# satshakit_micro.net
KiCad netlist of a schematic drawn in EAGLE
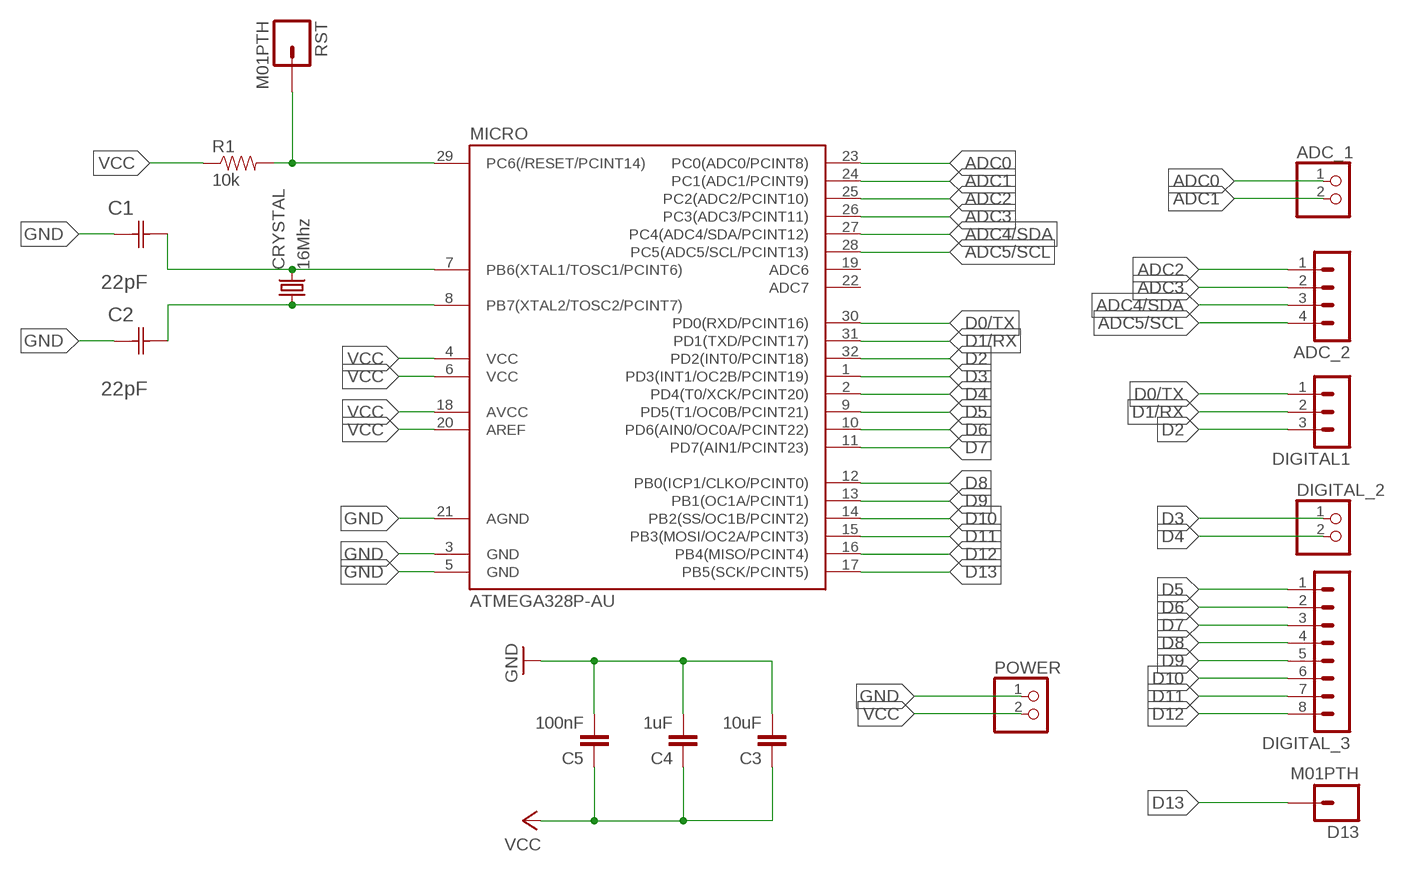
[diagram p0: schematic, sheet 1]

(export (version "E")
  (design (tool "Eeschema 10.0.6"))
  (components
    (comp (ref "ADC_1")
      (value "PINHD-1X2")
      (footprint "eagle-import:1X02")
      (libsource (lib "eagle-import") (part "PINHD-1X2"))
    )
    (comp (ref "ADC_2")
      (value "MA04-1")
      (footprint "eagle-import:MA04-1")
      (libsource (lib "eagle-import") (part "MA04-1"))
    )
    (comp (ref "C1")
      (value "22pF")
      (footprint "eagle-import:CAPC3216X178N")
      (fields (field (name "MPN") "0612ZC225MAT2A") (field (name "TOLERANCE") "±20%"))
      (libsource (lib "eagle-import") (part "0612ZC225MAT2A"))
    )
    (comp (ref "C2")
      (value "22pF")
      (footprint "eagle-import:CAPC3216X178N")
      (fields (field (name "MPN") "0612ZC225MAT2A") (field (name "TOLERANCE") "±20%"))
      (libsource (lib "eagle-import") (part "0612ZC225MAT2A"))
    )
    (comp (ref "C3")
      (value "10uF")
      (footprint "eagle-import:1206")
      (libsource (lib "eagle-import") (part "CAP1206"))
    )
    (comp (ref "C4")
      (value "1uF")
      (footprint "eagle-import:1206")
      (libsource (lib "eagle-import") (part "CAP1206"))
    )
    (comp (ref "C5")
      (value "100nF")
      (footprint "eagle-import:1206")
      (libsource (lib "eagle-import") (part "CAP1206"))
    )
    (comp (ref "CRYSTAL")
      (value "16Mhz")
      (footprint "eagle-import:CSM-7X-DU")
      (libsource (lib "eagle-import") (part "CSM-7X-DU"))
    )
    (comp (ref "D13")
      (value "M01PTH")
      (footprint "eagle-import:1X01")
      (libsource (lib "eagle-import") (part "M01PTH"))
    )
    (comp (ref "DIGITAL1")
      (value "MA03-1")
      (footprint "eagle-import:MA03-1")
      (libsource (lib "eagle-import") (part "MA03-1"))
    )
    (comp (ref "DIGITAL_2")
      (value "PINHD-1X2")
      (footprint "eagle-import:1X02")
      (libsource (lib "eagle-import") (part "PINHD-1X2"))
    )
    (comp (ref "DIGITAL_3")
      (value "MA08-1")
      (footprint "eagle-import:MA08-1")
      (libsource (lib "eagle-import") (part "MA08-1"))
    )
    (comp (ref "MICRO")
      (value "ATMEGA328P-AU")
      (footprint "eagle-import:TQFP32-08")
      (libsource (lib "eagle-import") (part "ATMEGA48/88/168-AU"))
    )
    (comp (ref "POWER")
      (value "PINHD-1X2")
      (footprint "eagle-import:1X02")
      (libsource (lib "eagle-import") (part "PINHD-1X2"))
    )
    (comp (ref "R1")
      (value "10k")
      (footprint "eagle-import:1206")
      (libsource (lib "eagle-import") (part "RESISTOR1206"))
    )
    (comp (ref "RST")
      (value "M01PTH")
      (footprint "eagle-import:1X01")
      (libsource (lib "eagle-import") (part "M01PTH"))
    )
  )
  (nets
    (net (code "1") (name "ADC0") (class "Default")
      (node (ref "ADC_1") (pin "1") (pinfunction "1_1") (pintype "passive"))
      (node (ref "MICRO") (pin "23") (pinfunction "PC0(ADC0/PCINT8)_23") (pintype "bidirectional"))
    )
    (net (code "2") (name "ADC1") (class "Default")
      (node (ref "ADC_1") (pin "2") (pinfunction "2_2") (pintype "passive"))
      (node (ref "MICRO") (pin "24") (pinfunction "PC1(ADC1/PCINT9)_24") (pintype "bidirectional"))
    )
    (net (code "3") (name "ADC2") (class "Default")
      (node (ref "ADC_2") (pin "1") (pinfunction "1_1") (pintype "passive"))
      (node (ref "MICRO") (pin "25") (pinfunction "PC2(ADC2/PCINT10)_25") (pintype "bidirectional"))
    )
    (net (code "4") (name "ADC3") (class "Default")
      (node (ref "ADC_2") (pin "2") (pinfunction "2_2") (pintype "passive"))
      (node (ref "MICRO") (pin "26") (pinfunction "PC3(ADC3/PCINT11)_26") (pintype "bidirectional"))
    )
    (net (code "5") (name "ADC4{slash}SDA") (class "Default")
      (node (ref "ADC_2") (pin "3") (pinfunction "3_3") (pintype "passive"))
      (node (ref "MICRO") (pin "27") (pinfunction "PC4(ADC4/SDA/PCINT12)_27") (pintype "bidirectional"))
    )
    (net (code "6") (name "ADC5{slash}SCL") (class "Default")
      (node (ref "ADC_2") (pin "4") (pinfunction "4_4") (pintype "passive"))
      (node (ref "MICRO") (pin "28") (pinfunction "PC5(ADC5/SCL/PCINT13)_28") (pintype "bidirectional"))
    )
    (net (code "7") (name "D0{slash}TX") (class "Default")
      (node (ref "DIGITAL1") (pin "1") (pinfunction "1_1") (pintype "passive"))
      (node (ref "MICRO") (pin "30") (pinfunction "PD0(RXD/PCINT16)_30") (pintype "bidirectional"))
    )
    (net (code "8") (name "D1{slash}RX") (class "Default")
      (node (ref "DIGITAL1") (pin "2") (pinfunction "2_2") (pintype "passive"))
      (node (ref "MICRO") (pin "31") (pinfunction "PD1(TXD/PCINT17)_31") (pintype "bidirectional"))
    )
    (net (code "9") (name "D2") (class "Default")
      (node (ref "DIGITAL1") (pin "3") (pinfunction "3_3") (pintype "passive"))
      (node (ref "MICRO") (pin "32") (pinfunction "PD2(INT0/PCINT18)_32") (pintype "bidirectional"))
    )
    (net (code "10") (name "D3") (class "Default")
      (node (ref "DIGITAL_2") (pin "1") (pinfunction "1_1") (pintype "passive"))
      (node (ref "MICRO") (pin "1") (pinfunction "PD3(INT1/OC2B/PCINT19)_1") (pintype "bidirectional"))
    )
    (net (code "11") (name "D4") (class "Default")
      (node (ref "DIGITAL_2") (pin "2") (pinfunction "2_2") (pintype "passive"))
      (node (ref "MICRO") (pin "2") (pinfunction "PD4(T0/XCK/PCINT20)_2") (pintype "bidirectional"))
    )
    (net (code "12") (name "D5") (class "Default")
      (node (ref "DIGITAL_3") (pin "1") (pinfunction "1_1") (pintype "passive"))
      (node (ref "MICRO") (pin "9") (pinfunction "PD5(T1/OC0B/PCINT21)_9") (pintype "bidirectional"))
    )
    (net (code "13") (name "D6") (class "Default")
      (node (ref "DIGITAL_3") (pin "2") (pinfunction "2_2") (pintype "passive"))
      (node (ref "MICRO") (pin "10") (pinfunction "PD6(AIN0/OC0A/PCINT22)_10") (pintype "bidirectional"))
    )
    (net (code "14") (name "D7") (class "Default")
      (node (ref "DIGITAL_3") (pin "3") (pinfunction "3_3") (pintype "passive"))
      (node (ref "MICRO") (pin "11") (pinfunction "PD7(AIN1/PCINT23)_11") (pintype "bidirectional"))
    )
    (net (code "15") (name "D8") (class "Default")
      (node (ref "DIGITAL_3") (pin "4") (pinfunction "4_4") (pintype "passive"))
      (node (ref "MICRO") (pin "12") (pinfunction "PB0(ICP1/CLKO/PCINT0)_12") (pintype "bidirectional"))
    )
    (net (code "16") (name "D9") (class "Default")
      (node (ref "DIGITAL_3") (pin "5") (pinfunction "5_5") (pintype "passive"))
      (node (ref "MICRO") (pin "13") (pinfunction "PB1(OC1A/PCINT1)_13") (pintype "bidirectional"))
    )
    (net (code "17") (name "D10") (class "Default")
      (node (ref "DIGITAL_3") (pin "6") (pinfunction "6_6") (pintype "passive"))
      (node (ref "MICRO") (pin "14") (pinfunction "PB2(SS/OC1B/PCINT2)_14") (pintype "bidirectional"))
    )
    (net (code "18") (name "D11") (class "Default")
      (node (ref "DIGITAL_3") (pin "7") (pinfunction "7_7") (pintype "passive"))
      (node (ref "MICRO") (pin "15") (pinfunction "PB3(MOSI/OC2A/PCINT3)_15") (pintype "bidirectional"))
    )
    (net (code "19") (name "D12") (class "Default")
      (node (ref "DIGITAL_3") (pin "8") (pinfunction "8_8") (pintype "passive"))
      (node (ref "MICRO") (pin "16") (pinfunction "PB4(MISO/PCINT4)_16") (pintype "bidirectional"))
    )
    (net (code "20") (name "D13") (class "Default")
      (node (ref "D13") (pin "1") (pinfunction "1_1") (pintype "passive"))
      (node (ref "MICRO") (pin "17") (pinfunction "PB5(SCK/PCINT5)_17") (pintype "bidirectional"))
    )
    (net (code "21") (name "GND") (class "Default")
      (node (ref "C1") (pin "1") (pinfunction "C1_1") (pintype "passive"))
      (node (ref "C2") (pin "1") (pinfunction "C1_1") (pintype "passive"))
      (node (ref "C3") (pin "2") (pinfunction "2_2") (pintype "passive"))
      (node (ref "C4") (pin "2") (pinfunction "2_2") (pintype "passive"))
      (node (ref "C5") (pin "2") (pinfunction "2_2") (pintype "passive"))
      (node (ref "MICRO") (pin "21") (pinfunction "AGND_21") (pintype "power_in"))
      (node (ref "MICRO") (pin "3") (pinfunction "GND_3") (pintype "power_in"))
      (node (ref "MICRO") (pin "5") (pinfunction "GND_5") (pintype "power_in"))
      (node (ref "POWER") (pin "1") (pinfunction "1_1") (pintype "passive"))
    )
    (net (code "22") (name "Net-(C1-C2)") (class "Default")
      (node (ref "C1") (pin "2") (pinfunction "C2_2") (pintype "passive"))
      (node (ref "CRYSTAL") (pin "2") (pinfunction "2_2") (pintype "passive"))
      (node (ref "MICRO") (pin "7") (pinfunction "PB6(XTAL1/TOSC1/PCINT6)_7") (pintype "bidirectional"))
    )
    (net (code "23") (name "Net-(C2-C2)") (class "Default")
      (node (ref "C2") (pin "2") (pinfunction "C2_2") (pintype "passive"))
      (node (ref "CRYSTAL") (pin "1") (pinfunction "1_1") (pintype "passive"))
      (node (ref "MICRO") (pin "8") (pinfunction "PB7(XTAL2/TOSC2/PCINT7)_8") (pintype "bidirectional"))
    )
    (net (code "24") (name "Net-(MICRO-PC6({slash}RESET{slash}PCINT14))") (class "Default")
      (node (ref "MICRO") (pin "29") (pinfunction "PC6(/RESET/PCINT14)_29") (pintype "bidirectional"))
      (node (ref "R1") (pin "2") (pinfunction "2_2") (pintype "passive"))
      (node (ref "RST") (pin "1") (pinfunction "1_1") (pintype "passive"))
    )
    (net (code "25") (name "VCC") (class "Default")
      (node (ref "C3") (pin "1") (pinfunction "1_1") (pintype "passive"))
      (node (ref "C4") (pin "1") (pinfunction "1_1") (pintype "passive"))
      (node (ref "C5") (pin "1") (pinfunction "1_1") (pintype "passive"))
      (node (ref "MICRO") (pin "18") (pinfunction "AVCC_18") (pintype "passive"))
      (node (ref "MICRO") (pin "20") (pinfunction "AREF_20") (pintype "passive"))
      (node (ref "MICRO") (pin "4") (pinfunction "VCC_4") (pintype "power_in"))
      (node (ref "MICRO") (pin "6") (pinfunction "VCC_6") (pintype "power_in"))
      (node (ref "POWER") (pin "2") (pinfunction "2_2") (pintype "passive"))
      (node (ref "R1") (pin "1") (pinfunction "1_1") (pintype "passive"))
    )
    (net (code "26") (name "unconnected-(MICRO-ADC6-Pad19)") (class "Default")
      (node (ref "MICRO") (pin "19") (pinfunction "ADC6_19") (pintype "passive"))
    )
    (net (code "27") (name "unconnected-(MICRO-ADC7-Pad22)") (class "Default")
      (node (ref "MICRO") (pin "22") (pinfunction "ADC7_22") (pintype "passive"))
    )
  )
)
